# GainDrain.net
KiCad netlist of a schematic drawn in Altium Designer
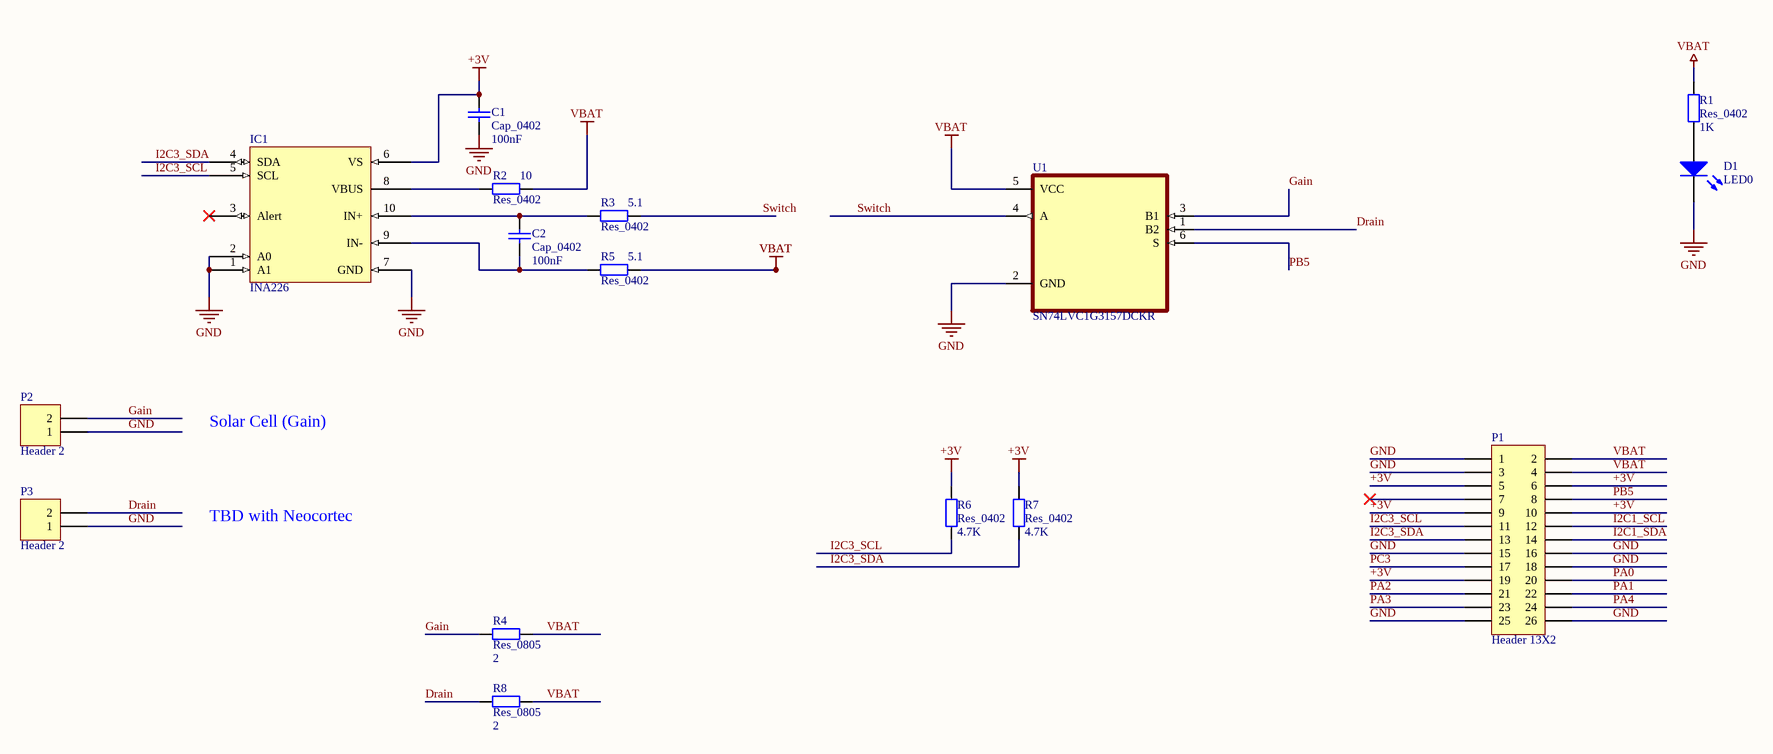
[diagram p0: GainDrain.SchDoc]

(export (version "E")
  (design (tool "Eeschema 10.0.6"))
  (components
    (comp (ref "C1")
      (value "Cap_0402")
      (footprint "0402")
      (description "Capacitor")
      (fields (field (name "ALTIUM_VALUE") "100nF") (field (name "PUBLISHER") "Altium Limited"))
      (libsource (lib "Schematic_Components") (part "Cap_0402"))
    )
    (comp (ref "C2")
      (value "Cap_0402")
      (footprint "0402")
      (description "Capacitor")
      (fields (field (name "ALTIUM_VALUE") "100nF") (field (name "PUBLISHER") "Altium Limited"))
      (libsource (lib "Schematic_Components") (part "Cap_0402"))
    )
    (comp (ref "D1")
      (value "LED0")
      (footprint "0603")
      (description "Typical INFRARED GaAs LED")
      (fields (field (name "PUBLISHER") "Altium Limited"))
      (libsource (lib "Schematic_Components") (part "LED0"))
    )
    (comp (ref "IC1")
      (value "INA226")
      (footprint "VSSOP-10")
      (description "Bi-Directional Current and Power Monitor")
      (libsource (lib "Schematic_Components") (part "INA226"))
    )
    (comp (ref "P1")
      (value "Header 13X2")
      (footprint "HDR2X13")
      (description "Header, 13-Pin, Dual row")
      (fields (field (name "PUBLISHER") "Altium Limited"))
      (libsource (lib "Miscellaneous Connectors") (part "Header 13X2"))
    )
    (comp (ref "P2")
      (value "Header 2")
      (footprint "HDR1X2")
      (description "Header, 2-Pin")
      (fields (field (name "PUBLISHER") "Altium Limited"))
      (libsource (lib "Miscellaneous Connectors") (part "Header 2"))
    )
    (comp (ref "P3")
      (value "Header 2")
      (footprint "HDR1X2")
      (description "Header, 2-Pin")
      (fields (field (name "PUBLISHER") "Altium Limited"))
      (libsource (lib "Miscellaneous Connectors") (part "Header 2"))
    )
    (comp (ref "R1")
      (value "Res_0402")
      (footprint "0402")
      (description "Resistor")
      (fields (field (name "ALTIUM_VALUE") "1K") (field (name "PUBLISHER") "Altium Limited"))
      (libsource (lib "") (part "Res_0402_1"))
    )
    (comp (ref "R2")
      (value "Res_0402")
      (footprint "0402")
      (description "Resistor")
      (fields (field (name "ALTIUM_VALUE") "10") (field (name "PUBLISHER") "Altium Limited"))
      (libsource (lib "Schematic_Components") (part "Res_0402"))
    )
    (comp (ref "R3")
      (value "Res_0402")
      (footprint "0402")
      (description "Resistor")
      (fields (field (name "ALTIUM_VALUE") "5.1") (field (name "PUBLISHER") "Altium Limited"))
      (libsource (lib "Schematic_Components") (part "Res_0402"))
    )
    (comp (ref "R4")
      (value "Res_0805")
      (footprint "0805")
      (description "Resistor")
      (fields (field (name "ALTIUM_VALUE") "2") (field (name "PUBLISHER") "Altium Limited"))
      (libsource (lib "Schematic_Components") (part "Res_0805"))
    )
    (comp (ref "R5")
      (value "Res_0402")
      (footprint "0402")
      (description "Resistor")
      (fields (field (name "ALTIUM_VALUE") "5.1") (field (name "PUBLISHER") "Altium Limited"))
      (libsource (lib "Schematic_Components") (part "Res_0402"))
    )
    (comp (ref "R6")
      (value "Res_0402")
      (footprint "0402")
      (description "Resistor")
      (fields (field (name "ALTIUM_VALUE") "4.7K") (field (name "PUBLISHER") "Altium Limited"))
      (libsource (lib "") (part "Res_0402_1"))
    )
    (comp (ref "R7")
      (value "Res_0402")
      (footprint "0402")
      (description "Resistor")
      (fields (field (name "ALTIUM_VALUE") "4.7K") (field (name "PUBLISHER") "Altium Limited"))
      (libsource (lib "") (part "Res_0402_1"))
    )
    (comp (ref "R8")
      (value "Res_0805")
      (footprint "0805")
      (description "Resistor")
      (fields (field (name "ALTIUM_VALUE") "2") (field (name "PUBLISHER") "Altium Limited"))
      (libsource (lib "Schematic_Components") (part "Res_0805"))
    )
    (comp (ref "U1")
      (value "SN74LVC1G3157DCKR")
      (footprint "SOT65P210X110-6N")
      (description "5 Vï¼Œ2ï¼š1ï¼ˆSPDTï¼‰ï¼Œ1é€šé“é€šç”¨æ¨¡æ“¬é–‹é—œ6-SC70 -40è‡³125")
      (fields (field (name "MF") "Texas Instruments"))
      (libsource (lib "SN74LVC1G3157DCKR") (part "SN74LVC1G3157DCKR"))
    )
  )
  (nets
    (net (code "1") (name "+3V") (class "Default")
      (node (ref "C1") (pin "2") (pinfunction "2_2") (pintype "passive"))
      (node (ref "IC1") (pin "6") (pinfunction "VS_6") (pintype "input"))
      (node (ref "P1") (pin "10") (pinfunction "10_10") (pintype "passive"))
      (node (ref "P1") (pin "19") (pinfunction "19_19") (pintype "passive"))
      (node (ref "P1") (pin "5") (pinfunction "5_5") (pintype "passive"))
      (node (ref "P1") (pin "6") (pinfunction "6_6") (pintype "passive"))
      (node (ref "P1") (pin "9") (pinfunction "9_9") (pintype "passive"))
      (node (ref "R6") (pin "2") (pinfunction "2_2") (pintype "passive"))
      (node (ref "R7") (pin "2") (pinfunction "2_2") (pintype "passive"))
    )
    (net (code "2") (name "/Drain") (class "Default")
      (node (ref "P3") (pin "2") (pinfunction "2_2") (pintype "passive"))
      (node (ref "R8") (pin "2") (pinfunction "2_2") (pintype "passive"))
      (node (ref "U1") (pin "1") (pinfunction "B2_1") (pintype "input"))
    )
    (net (code "3") (name "/Gain") (class "Default")
      (node (ref "P2") (pin "2") (pinfunction "2_2") (pintype "passive"))
      (node (ref "R4") (pin "2") (pinfunction "2_2") (pintype "passive"))
      (node (ref "U1") (pin "3") (pinfunction "B1_3") (pintype "input"))
    )
    (net (code "4") (name "/I2C1_SCL") (class "Default")
      (node (ref "P1") (pin "12") (pinfunction "12_12") (pintype "passive"))
    )
    (net (code "5") (name "/I2C1_SDA") (class "Default")
      (node (ref "P1") (pin "14") (pinfunction "14_14") (pintype "passive"))
    )
    (net (code "6") (name "/I2C3_SCL") (class "Default")
      (node (ref "IC1") (pin "5") (pinfunction "SCL_5") (pintype "input"))
      (node (ref "P1") (pin "11") (pinfunction "11_11") (pintype "passive"))
      (node (ref "R6") (pin "1") (pinfunction "1_1") (pintype "passive"))
    )
    (net (code "7") (name "/I2C3_SDA") (class "Default")
      (node (ref "IC1") (pin "4") (pinfunction "SDA_4") (pintype "bidirectional"))
      (node (ref "P1") (pin "13") (pinfunction "13_13") (pintype "passive"))
      (node (ref "R7") (pin "1") (pinfunction "1_1") (pintype "passive"))
    )
    (net (code "8") (name "/PA0") (class "Default")
      (node (ref "P1") (pin "20") (pinfunction "20_20") (pintype "passive"))
    )
    (net (code "9") (name "/PA1") (class "Default")
      (node (ref "P1") (pin "22") (pinfunction "22_22") (pintype "passive"))
    )
    (net (code "10") (name "/PA2") (class "Default")
      (node (ref "P1") (pin "21") (pinfunction "21_21") (pintype "passive"))
    )
    (net (code "11") (name "/PA3") (class "Default")
      (node (ref "P1") (pin "23") (pinfunction "23_23") (pintype "passive"))
    )
    (net (code "12") (name "/PA4") (class "Default")
      (node (ref "P1") (pin "24") (pinfunction "24_24") (pintype "passive"))
    )
    (net (code "13") (name "/PB5") (class "Default")
      (node (ref "P1") (pin "8") (pinfunction "8_8") (pintype "passive"))
      (node (ref "U1") (pin "6") (pinfunction "S_6") (pintype "input"))
    )
    (net (code "14") (name "/PC3") (class "Default")
      (node (ref "P1") (pin "17") (pinfunction "17_17") (pintype "passive"))
    )
    (net (code "15") (name "/Switch") (class "Default")
      (node (ref "R3") (pin "2") (pinfunction "2_2") (pintype "passive"))
      (node (ref "U1") (pin "4") (pinfunction "A_4") (pintype "output"))
    )
    (net (code "16") (name "GND") (class "Default")
      (node (ref "C1") (pin "1") (pinfunction "1_1") (pintype "passive"))
      (node (ref "D1") (pin "1") (pinfunction "K_1") (pintype "passive"))
      (node (ref "IC1") (pin "1") (pinfunction "A1_1") (pintype "input"))
      (node (ref "IC1") (pin "2") (pinfunction "A0_2") (pintype "input"))
      (node (ref "IC1") (pin "7") (pinfunction "GND_7") (pintype "input"))
      (node (ref "P1") (pin "1") (pinfunction "1_1") (pintype "passive"))
      (node (ref "P1") (pin "15") (pinfunction "15_15") (pintype "passive"))
      (node (ref "P1") (pin "16") (pinfunction "16_16") (pintype "passive"))
      (node (ref "P1") (pin "18") (pinfunction "18_18") (pintype "passive"))
      (node (ref "P1") (pin "25") (pinfunction "25_25") (pintype "passive"))
      (node (ref "P1") (pin "26") (pinfunction "26_26") (pintype "passive"))
      (node (ref "P1") (pin "3") (pinfunction "3_3") (pintype "passive"))
      (node (ref "P2") (pin "1") (pinfunction "1_1") (pintype "passive"))
      (node (ref "P3") (pin "1") (pinfunction "1_1") (pintype "passive"))
      (node (ref "U1") (pin "2") (pinfunction "GND_2") (pintype "power_in"))
    )
    (net (code "17") (name "Net-(D1-A)") (class "Default")
      (node (ref "D1") (pin "2") (pinfunction "A_2") (pintype "passive"))
      (node (ref "R1") (pin "1") (pinfunction "1_1") (pintype "passive"))
    )
    (net (code "18") (name "Net-(IC1-IN+)") (class "Default")
      (node (ref "C2") (pin "2") (pinfunction "2_2") (pintype "passive"))
      (node (ref "IC1") (pin "10") (pinfunction "IN+_10") (pintype "input"))
      (node (ref "R3") (pin "1") (pinfunction "1_1") (pintype "passive"))
    )
    (net (code "19") (name "Net-(IC1-IN-)") (class "Default")
      (node (ref "C2") (pin "1") (pinfunction "1_1") (pintype "passive"))
      (node (ref "IC1") (pin "9") (pinfunction "IN-_9") (pintype "input"))
      (node (ref "R5") (pin "1") (pinfunction "1_1") (pintype "passive"))
    )
    (net (code "20") (name "Net-(IC1-VBUS)") (class "Default")
      (node (ref "IC1") (pin "8") (pinfunction "VBUS_8") (pintype "power_in"))
      (node (ref "R2") (pin "1") (pinfunction "1_1") (pintype "passive"))
    )
    (net (code "21") (name "VBAT") (class "Default")
      (node (ref "P1") (pin "2") (pinfunction "2_2") (pintype "passive"))
      (node (ref "P1") (pin "4") (pinfunction "4_4") (pintype "passive"))
      (node (ref "R1") (pin "2") (pinfunction "2_2") (pintype "passive"))
      (node (ref "R2") (pin "2") (pinfunction "2_2") (pintype "passive"))
      (node (ref "R4") (pin "1") (pinfunction "1_1") (pintype "passive"))
      (node (ref "R5") (pin "2") (pinfunction "2_2") (pintype "passive"))
      (node (ref "R8") (pin "1") (pinfunction "1_1") (pintype "passive"))
      (node (ref "U1") (pin "5") (pinfunction "VCC_5") (pintype "power_in"))
    )
    (net (code "22") (name "unconnected-(IC1-Alert-Pad3)") (class "Default")
      (node (ref "IC1") (pin "3") (pinfunction "Alert_3") (pintype "bidirectional+no_connect"))
    )
    (net (code "23") (name "unconnected-(P1-Pad7)") (class "Default")
      (node (ref "P1") (pin "7") (pinfunction "7_7") (pintype "passive+no_connect"))
    )
  )
)
